# powerBoard.net
KiCad netlist of a schematic drawn in EAGLE
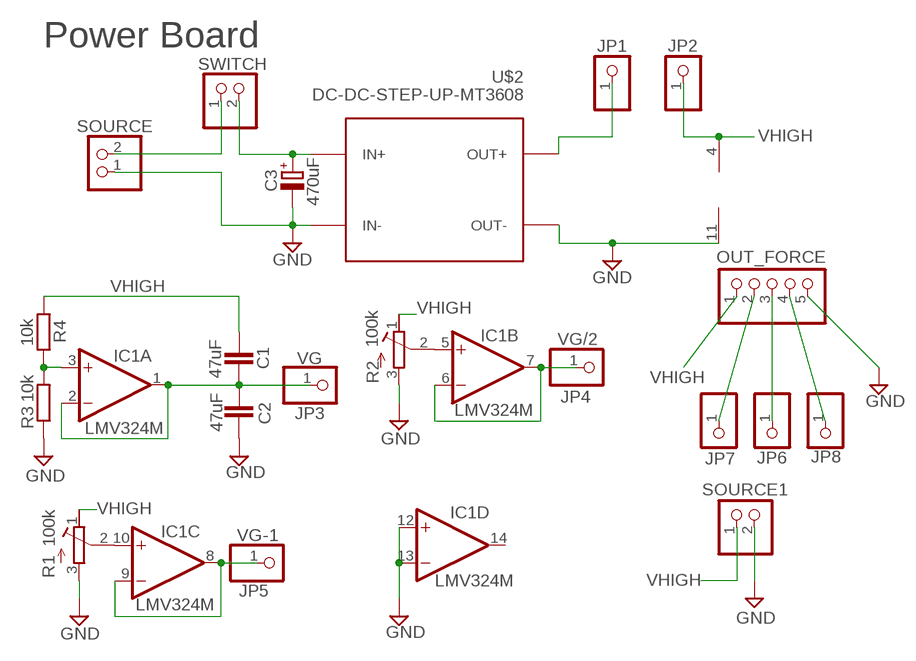
[diagram p0: schematic, sheet 1]

(export (version "E")
  (design (tool "Eeschema 10.0.6"))
  (components
    (comp (ref "C1")
      (value "47uF")
      (footprint "eagle-import:C0805")
      (libsource (lib "eagle-import") (part "C-EUC0805"))
    )
    (comp (ref "C2")
      (value "47uF")
      (footprint "eagle-import:C0805")
      (libsource (lib "eagle-import") (part "C-EUC0805"))
    )
    (comp (ref "C3")
      (value "470uF")
      (footprint "eagle-import:E2,5-7")
      (libsource (lib "eagle-import") (part "CPOL-EUE2.5-7"))
    )
    (comp (ref "IC1")
      (value "LMV324M")
      (footprint "eagle-import:SO14")
      (libsource (lib "eagle-import") (part "LMV324?M"))
    )
    (comp (ref "JP1")
      (value "PINHD-1X1")
      (footprint "eagle-import:1X01")
      (libsource (lib "eagle-import") (part "PINHD-1X1"))
    )
    (comp (ref "JP2")
      (value "PINHD-1X1")
      (footprint "eagle-import:1X01")
      (libsource (lib "eagle-import") (part "PINHD-1X1"))
    )
    (comp (ref "JP3")
      (value "PINHD-1X1")
      (footprint "eagle-import:1X01")
      (libsource (lib "eagle-import") (part "PINHD-1X1"))
    )
    (comp (ref "JP4")
      (value "PINHD-1X1")
      (footprint "eagle-import:1X01")
      (libsource (lib "eagle-import") (part "PINHD-1X1"))
    )
    (comp (ref "JP5")
      (value "PINHD-1X1")
      (footprint "eagle-import:1X01")
      (libsource (lib "eagle-import") (part "PINHD-1X1"))
    )
    (comp (ref "JP6")
      (value "PINHD-1X1")
      (footprint "eagle-import:1X01")
      (libsource (lib "eagle-import") (part "PINHD-1X1"))
    )
    (comp (ref "JP7")
      (value "PINHD-1X1")
      (footprint "eagle-import:1X01")
      (libsource (lib "eagle-import") (part "PINHD-1X1"))
    )
    (comp (ref "JP8")
      (value "PINHD-1X1")
      (footprint "eagle-import:1X01")
      (libsource (lib "eagle-import") (part "PINHD-1X1"))
    )
    (comp (ref "OUT_FORCE")
      (value "PINHD-1X5")
      (footprint "eagle-import:1X05")
      (libsource (lib "eagle-import") (part "PINHD-1X5"))
    )
    (comp (ref "R1")
      (value "100k")
      (footprint "eagle-import:RTRIM3006P")
      (libsource (lib "eagle-import") (part "R-TRIMM3006P"))
    )
    (comp (ref "R2")
      (value "100k")
      (footprint "eagle-import:RTRIM3006P")
      (libsource (lib "eagle-import") (part "R-TRIMM3006P"))
    )
    (comp (ref "R3")
      (value "10k")
      (footprint "eagle-import:R0805")
      (libsource (lib "eagle-import") (part "R-EU_R0805"))
    )
    (comp (ref "R4")
      (value "10k")
      (footprint "eagle-import:R0805")
      (libsource (lib "eagle-import") (part "R-EU_R0805"))
    )
    (comp (ref "SOURCE")
      (value "PINHD-1X2")
      (footprint "eagle-import:1X02")
      (libsource (lib "eagle-import") (part "PINHD-1X2"))
    )
    (comp (ref "SOURCE1")
      (value "PINHD-1X2")
      (footprint "eagle-import:1X02")
      (libsource (lib "eagle-import") (part "PINHD-1X2"))
    )
    (comp (ref "SWITCH")
      (value "PINHD-1X2")
      (footprint "eagle-import:1X02")
      (libsource (lib "eagle-import") (part "PINHD-1X2"))
    )
    (comp (ref "U$2")
      (value "DC-DC-STEP-UP-MT3608")
      (footprint "eagle-import:DC-DC-STEP-UP-MT3608")
      (libsource (lib "eagle-import") (part "DC-DC-STEP-UP-MT3608"))
    )
  )
  (nets
    (net (code "1") (name "/VG") (class "Default")
      (node (ref "C1") (pin "2") (pinfunction "2_2") (pintype "passive"))
      (node (ref "C2") (pin "1") (pinfunction "1_1") (pintype "passive"))
      (node (ref "IC1") (pin "1") (pinfunction "OUT_1") (pintype "output"))
      (node (ref "IC1") (pin "2") (pinfunction "-IN_2") (pintype "input"))
      (node (ref "JP3") (pin "1") (pinfunction "1_1") (pintype "passive"))
    )
    (net (code "2") (name "/VG-1") (class "Default")
      (node (ref "IC1") (pin "8") (pinfunction "OUT_8") (pintype "output"))
      (node (ref "IC1") (pin "9") (pinfunction "-IN_9") (pintype "input"))
      (node (ref "JP5") (pin "1") (pinfunction "1_1") (pintype "passive"))
    )
    (net (code "3") (name "/VG{slash}2") (class "Default")
      (node (ref "IC1") (pin "6") (pinfunction "-IN_6") (pintype "input"))
      (node (ref "IC1") (pin "7") (pinfunction "OUT_7") (pintype "output"))
      (node (ref "JP4") (pin "1") (pinfunction "1_1") (pintype "passive"))
    )
    (net (code "4") (name "/VHIGH") (class "Default")
      (node (ref "C1") (pin "1") (pinfunction "1_1") (pintype "passive"))
      (node (ref "IC1") (pin "4") (pinfunction "V+_4") (pintype "power_in"))
      (node (ref "JP2") (pin "1") (pinfunction "1_1") (pintype "passive"))
      (node (ref "OUT_FORCE") (pin "1") (pinfunction "1_1") (pintype "passive"))
      (node (ref "R1") (pin "1") (pinfunction "E_1") (pintype "passive"))
      (node (ref "R2") (pin "1") (pinfunction "E_1") (pintype "passive"))
      (node (ref "R4") (pin "1") (pinfunction "1_1") (pintype "passive"))
      (node (ref "SOURCE1") (pin "1") (pinfunction "1_1") (pintype "passive"))
    )
    (net (code "5") (name "GND") (class "Default")
      (node (ref "C2") (pin "2") (pinfunction "2_2") (pintype "passive"))
      (node (ref "C3") (pin "-") (pinfunction "-_-") (pintype "passive"))
      (node (ref "IC1") (pin "11") (pinfunction "V-_11") (pintype "power_in"))
      (node (ref "IC1") (pin "12") (pinfunction "+IN_12") (pintype "input"))
      (node (ref "IC1") (pin "13") (pinfunction "-IN_13") (pintype "input"))
      (node (ref "OUT_FORCE") (pin "5") (pinfunction "5_5") (pintype "passive"))
      (node (ref "R1") (pin "3") (pinfunction "A_3") (pintype "passive"))
      (node (ref "R2") (pin "3") (pinfunction "A_3") (pintype "passive"))
      (node (ref "R3") (pin "1") (pinfunction "1_1") (pintype "passive"))
      (node (ref "SOURCE") (pin "1") (pinfunction "1_1") (pintype "passive"))
      (node (ref "SOURCE1") (pin "2") (pinfunction "2_2") (pintype "passive"))
      (node (ref "U$2") (pin "IN-") (pinfunction "IN-_IN-") (pintype "bidirectional"))
      (node (ref "U$2") (pin "OUT-") (pinfunction "OUT-_OUT-") (pintype "bidirectional"))
    )
    (net (code "6") (name "Net-(C3-Pad+)") (class "Default")
      (node (ref "C3") (pin "+") (pinfunction "+_+") (pintype "passive"))
      (node (ref "SWITCH") (pin "2") (pinfunction "2_2") (pintype "passive"))
      (node (ref "U$2") (pin "IN+") (pinfunction "IN+_IN+") (pintype "bidirectional"))
    )
    (net (code "7") (name "Net-(IC1A-+IN)") (class "Default")
      (node (ref "IC1") (pin "3") (pinfunction "+IN_3") (pintype "input"))
      (node (ref "R3") (pin "2") (pinfunction "2_2") (pintype "passive"))
      (node (ref "R4") (pin "2") (pinfunction "2_2") (pintype "passive"))
    )
    (net (code "8") (name "Net-(IC1B-+IN)") (class "Default")
      (node (ref "IC1") (pin "5") (pinfunction "+IN_5") (pintype "input"))
      (node (ref "R2") (pin "2") (pinfunction "S_2") (pintype "passive"))
    )
    (net (code "9") (name "Net-(IC1C-+IN)") (class "Default")
      (node (ref "IC1") (pin "10") (pinfunction "+IN_10") (pintype "input"))
      (node (ref "R1") (pin "2") (pinfunction "S_2") (pintype "passive"))
    )
    (net (code "10") (name "Net-(JP1-Pad1)") (class "Default")
      (node (ref "JP1") (pin "1") (pinfunction "1_1") (pintype "passive"))
      (node (ref "U$2") (pin "OUT+") (pinfunction "OUT+_OUT+") (pintype "bidirectional"))
    )
    (net (code "11") (name "Net-(JP6-Pad1)") (class "Default")
      (node (ref "JP6") (pin "1") (pinfunction "1_1") (pintype "passive"))
      (node (ref "OUT_FORCE") (pin "3") (pinfunction "3_3") (pintype "passive"))
    )
    (net (code "12") (name "Net-(JP7-Pad1)") (class "Default")
      (node (ref "JP7") (pin "1") (pinfunction "1_1") (pintype "passive"))
      (node (ref "OUT_FORCE") (pin "2") (pinfunction "2_2") (pintype "passive"))
    )
    (net (code "13") (name "Net-(JP8-Pad1)") (class "Default")
      (node (ref "JP8") (pin "1") (pinfunction "1_1") (pintype "passive"))
      (node (ref "OUT_FORCE") (pin "4") (pinfunction "4_4") (pintype "passive"))
    )
    (net (code "14") (name "Net-(SOURCE-Pad2)") (class "Default")
      (node (ref "SOURCE") (pin "2") (pinfunction "2_2") (pintype "passive"))
      (node (ref "SWITCH") (pin "1") (pinfunction "1_1") (pintype "passive"))
    )
    (net (code "15") (name "unconnected-(IC1D-OUT-Pad14)") (class "Default")
      (node (ref "IC1") (pin "14") (pinfunction "OUT_14") (pintype "output"))
    )
  )
)
